# DribblerInterface.net
KiCad netlist of a schematic drawn in Altium Designer
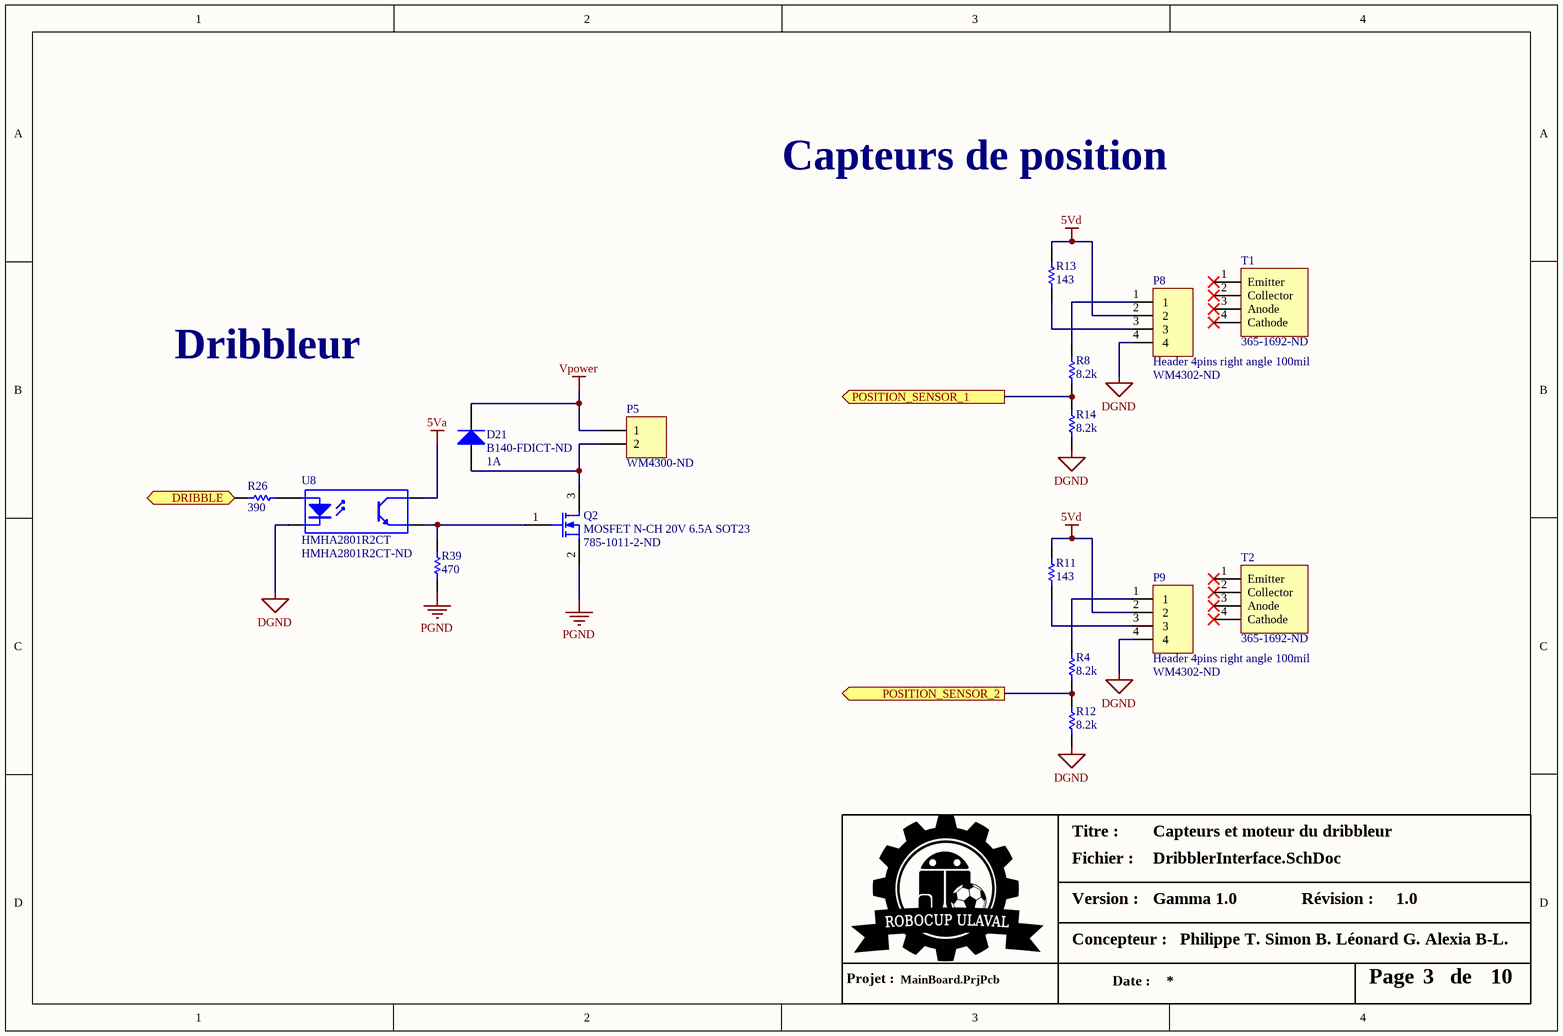
[diagram p0: DribblerInterface.SchDoc]

(export (version "E")
  (design (tool "Eeschema 10.0.6"))
  (components
    (comp (ref "D21")
      (value "B140-13-F")
      (footprint "SMA")
      (description "DIODE SCHOTTKY 40V 1A SMA")
      (fields
        (field (name "MANUFACTURER") "Diodes Incorporated")
        (field (name "SUPPLIER PART NUMBER 1") "B140-FDICT-ND")
        (field (name "CURRENT - AVERAGE RECTIFIED (IO)") "1A")
      )
      (libsource (lib "MainBoard") (part "B140-13-F"))
    )
    (comp (ref "P5")
      (value "Header 2 Right Angle")
      (footprint "0.156mil header right angle")
      (description "Header, 2-Pin, 0.156mil, Right Angle")
      (fields (field (name "SUPPLIER PART NUMBER 1") "WM4300-ND"))
      (libsource (lib "MainBoard") (part "Header 2pin 0.156 Right Angle"))
    )
    (comp (ref "P8")
      (value "Header 4pins right angle 100mil")
      (footprint "HDR1x4_Right_Angle")
      (fields (field (name "SUPPLIER PART NUMBER 1") "WM4302-ND"))
      (libsource (lib "MainBoard") (part "Header 4pins right angle 100mil"))
    )
    (comp (ref "P9")
      (value "Header 4pins right angle 100mil")
      (footprint "HDR1x4_Right_Angle")
      (fields (field (name "SUPPLIER PART NUMBER 1") "WM4302-ND"))
      (libsource (lib "MainBoard") (part "Header 4pins right angle 100mil"))
    )
    (comp (ref "Q2")
      (value "MOSFET N-CH 20V 6.5A SOT23")
      (footprint "SOT-23-3")
      (fields (field (name "SUPPLIER PART NUMBER 1") "785-1011-2-ND"))
      (libsource (lib "MainBoard") (part "AO3416"))
    )
    (comp (ref "R4")
      (value "RC0603JR-078K2L")
      (footprint "0603")
      (description "RES SMD 8.2K OHM 5% 1/10W 0603")
      (fields
        (field (name "MANUFACTURER") "Yageo")
        (field (name "TOLERANCE") "±5%")
        (field (name "RESISTANCE (OHMS)") "8.2k")
      )
      (libsource (lib "ResCap") (part "RC0603JR-078K2L"))
    )
    (comp (ref "R8")
      (value "RC0603JR-078K2L")
      (footprint "0603")
      (description "RES SMD 8.2K OHM 5% 1/10W 0603")
      (fields
        (field (name "MANUFACTURER") "Yageo")
        (field (name "TOLERANCE") "±5%")
        (field (name "RESISTANCE (OHMS)") "8.2k")
      )
      (libsource (lib "ResCap") (part "RC0603JR-078K2L"))
    )
    (comp (ref "R11")
      (value "RC0603FR-07143RL")
      (footprint "0603")
      (description "RES SMD 143 OHM 1% 1/10W 0603")
      (fields
        (field (name "MANUFACTURER") "Yageo")
        (field (name "TOLERANCE") "±1%")
        (field (name "RESISTANCE (OHMS)") "143")
      )
      (libsource (lib "ResCap") (part "RC0603FR-07143RL"))
    )
    (comp (ref "R12")
      (value "RC0603JR-078K2L")
      (footprint "0603")
      (description "RES SMD 8.2K OHM 5% 1/10W 0603")
      (fields
        (field (name "MANUFACTURER") "Yageo")
        (field (name "TOLERANCE") "±5%")
        (field (name "RESISTANCE (OHMS)") "8.2k")
      )
      (libsource (lib "ResCap") (part "RC0603JR-078K2L"))
    )
    (comp (ref "R13")
      (value "RC0603FR-07143RL")
      (footprint "0603")
      (description "RES SMD 143 OHM 1% 1/10W 0603")
      (fields
        (field (name "MANUFACTURER") "Yageo")
        (field (name "TOLERANCE") "±1%")
        (field (name "RESISTANCE (OHMS)") "143")
      )
      (libsource (lib "ResCap") (part "RC0603FR-07143RL"))
    )
    (comp (ref "R14")
      (value "RC0603JR-078K2L")
      (footprint "0603")
      (description "RES SMD 8.2K OHM 5% 1/10W 0603")
      (fields
        (field (name "MANUFACTURER") "Yageo")
        (field (name "TOLERANCE") "±5%")
        (field (name "RESISTANCE (OHMS)") "8.2k")
      )
      (libsource (lib "ResCap") (part "RC0603JR-078K2L"))
    )
    (comp (ref "R26")
      (value "RC0603JR-07390RL")
      (footprint "0603")
      (description "RES SMD 390 OHM 5% 1/10W 0603")
      (fields
        (field (name "MANUFACTURER") "Yageo")
        (field (name "TOLERANCE") "±5%")
        (field (name "RESISTANCE (OHMS)") "390")
      )
      (libsource (lib "ResCap") (part "RC0603JR-07390RL"))
    )
    (comp (ref "R39")
      (value "RC0603JR-07470RL")
      (footprint "0603")
      (description "RES SMD 470 OHM 5% 1/10W 0603")
      (fields
        (field (name "MANUFACTURER") "Yageo")
        (field (name "TOLERANCE") "±5%")
        (field (name "RESISTANCE (OHMS)") "470")
      )
      (libsource (lib "ResCap") (part "RC0603JR-07470RL"))
    )
    (comp (ref "T1")
      (value "OPB732WZ")
      (description "SNSR OPTO TRANS 76.2MM REFL C-MT")
      (fields
        (field (name "MANUFACTURER") "TT Electronics/Optek Technology")
        (field (name "SUPPLIER PART NUMBER 1") "365-1692-ND")
      )
      (libsource (lib "MainBoard") (part "OPB732WZ"))
    )
    (comp (ref "T2")
      (value "OPB732WZ")
      (description "SNSR OPTO TRANS 76.2MM REFL C-MT")
      (fields
        (field (name "MANUFACTURER") "TT Electronics/Optek Technology")
        (field (name "SUPPLIER PART NUMBER 1") "365-1692-ND")
      )
      (libsource (lib "MainBoard") (part "OPB732WZ"))
    )
    (comp (ref "U8")
      (value "HMHA2801R2CT")
      (footprint "SOIC127P700X220-4N")
      (description "OPTOISOLATOR 3.75KV TRANS 4-SO")
      (fields (field (name "SUPPLIER PART NUMBER 1") "HMHA2801R2CT-ND"))
      (libsource (lib "MainBoard") (part "HMHA2801R2CT"))
    )
  )
  (nets
    (net (code "1") (name "/DRIBBLE") (class "Default")
      (node (ref "R26") (pin "1") (pinfunction "1_1") (pintype "passive"))
    )
    (net (code "2") (name "/POSITION_SENSOR_1") (class "Default")
      (node (ref "R14") (pin "2") (pinfunction "2_2") (pintype "passive"))
      (node (ref "R8") (pin "1") (pinfunction "1_1") (pintype "passive"))
    )
    (net (code "3") (name "/POSITION_SENSOR_2") (class "Default")
      (node (ref "R12") (pin "2") (pinfunction "2_2") (pintype "passive"))
      (node (ref "R4") (pin "1") (pinfunction "1_1") (pintype "passive"))
    )
    (net (code "4") (name "5Va") (class "Default")
      (node (ref "U8") (pin "4") (pinfunction "C_4") (pintype "passive"))
    )
    (net (code "5") (name "5Vd") (class "Default")
      (node (ref "P8") (pin "2") (pinfunction "2_2") (pintype "passive"))
      (node (ref "P9") (pin "2") (pinfunction "2_2") (pintype "passive"))
      (node (ref "R11") (pin "2") (pinfunction "2_2") (pintype "passive"))
      (node (ref "R13") (pin "2") (pinfunction "2_2") (pintype "passive"))
    )
    (net (code "6") (name "DGND") (class "Default")
      (node (ref "P8") (pin "4") (pinfunction "4_4") (pintype "passive"))
      (node (ref "P9") (pin "4") (pinfunction "4_4") (pintype "passive"))
      (node (ref "R12") (pin "1") (pinfunction "1_1") (pintype "passive"))
      (node (ref "R14") (pin "1") (pinfunction "1_1") (pintype "passive"))
      (node (ref "U8") (pin "2") (pinfunction "K_2") (pintype "passive"))
    )
    (net (code "7") (name "Net-(D21-A)") (class "Default")
      (node (ref "D21") (pin "1") (pinfunction "A_1") (pintype "passive"))
      (node (ref "P5") (pin "2") (pinfunction "2_2") (pintype "passive"))
      (node (ref "Q2") (pin "3") (pinfunction "D_3") (pintype "passive"))
    )
    (net (code "8") (name "Net-(P8-Pad1)") (class "Default")
      (node (ref "P8") (pin "1") (pinfunction "1_1") (pintype "passive"))
      (node (ref "R8") (pin "2") (pinfunction "2_2") (pintype "passive"))
    )
    (net (code "9") (name "Net-(P8-Pad3)") (class "Default")
      (node (ref "P8") (pin "3") (pinfunction "3_3") (pintype "passive"))
      (node (ref "R13") (pin "1") (pinfunction "1_1") (pintype "passive"))
    )
    (net (code "10") (name "Net-(P9-Pad1)") (class "Default")
      (node (ref "P9") (pin "1") (pinfunction "1_1") (pintype "passive"))
      (node (ref "R4") (pin "2") (pinfunction "2_2") (pintype "passive"))
    )
    (net (code "11") (name "Net-(P9-Pad3)") (class "Default")
      (node (ref "P9") (pin "3") (pinfunction "3_3") (pintype "passive"))
      (node (ref "R11") (pin "1") (pinfunction "1_1") (pintype "passive"))
    )
    (net (code "12") (name "Net-(Q2-G)") (class "Default")
      (node (ref "Q2") (pin "1") (pinfunction "G_1") (pintype "passive"))
      (node (ref "R39") (pin "2") (pinfunction "2_2") (pintype "passive"))
      (node (ref "U8") (pin "3") (pinfunction "E_3") (pintype "passive"))
    )
    (net (code "13") (name "Net-(U8-A)") (class "Default")
      (node (ref "R26") (pin "2") (pinfunction "2_2") (pintype "passive"))
      (node (ref "U8") (pin "1") (pinfunction "A_1") (pintype "passive"))
    )
    (net (code "14") (name "PGND") (class "Default")
      (node (ref "Q2") (pin "2") (pinfunction "S_2") (pintype "passive"))
      (node (ref "R39") (pin "1") (pinfunction "1_1") (pintype "passive"))
    )
    (net (code "15") (name "Vpower") (class "Default")
      (node (ref "D21") (pin "2") (pinfunction "K_2") (pintype "passive"))
      (node (ref "P5") (pin "1") (pinfunction "1_1") (pintype "passive"))
    )
    (net (code "16") (name "unconnected-(T1-Anode-Pad3)") (class "Default")
      (node (ref "T1") (pin "3") (pinfunction "Anode_3") (pintype "power_in+no_connect"))
    )
    (net (code "17") (name "unconnected-(T1-Cathode-Pad4)") (class "Default")
      (node (ref "T1") (pin "4") (pinfunction "Cathode_4") (pintype "power_in+no_connect"))
    )
    (net (code "18") (name "unconnected-(T1-Collector-Pad2)") (class "Default")
      (node (ref "T1") (pin "2") (pinfunction "Collector_2") (pintype "passive+no_connect"))
    )
    (net (code "19") (name "unconnected-(T1-Emitter-Pad1)") (class "Default")
      (node (ref "T1") (pin "1") (pinfunction "Emitter_1") (pintype "passive+no_connect"))
    )
    (net (code "20") (name "unconnected-(T2-Anode-Pad3)") (class "Default")
      (node (ref "T2") (pin "3") (pinfunction "Anode_3") (pintype "power_in+no_connect"))
    )
    (net (code "21") (name "unconnected-(T2-Cathode-Pad4)") (class "Default")
      (node (ref "T2") (pin "4") (pinfunction "Cathode_4") (pintype "power_in+no_connect"))
    )
    (net (code "22") (name "unconnected-(T2-Collector-Pad2)") (class "Default")
      (node (ref "T2") (pin "2") (pinfunction "Collector_2") (pintype "passive+no_connect"))
    )
    (net (code "23") (name "unconnected-(T2-Emitter-Pad1)") (class "Default")
      (node (ref "T2") (pin "1") (pinfunction "Emitter_1") (pintype "passive+no_connect"))
    )
  )
)
